# 05_LMS7002M_Misc.net
KiCad netlist of a schematic drawn in Altium Designer
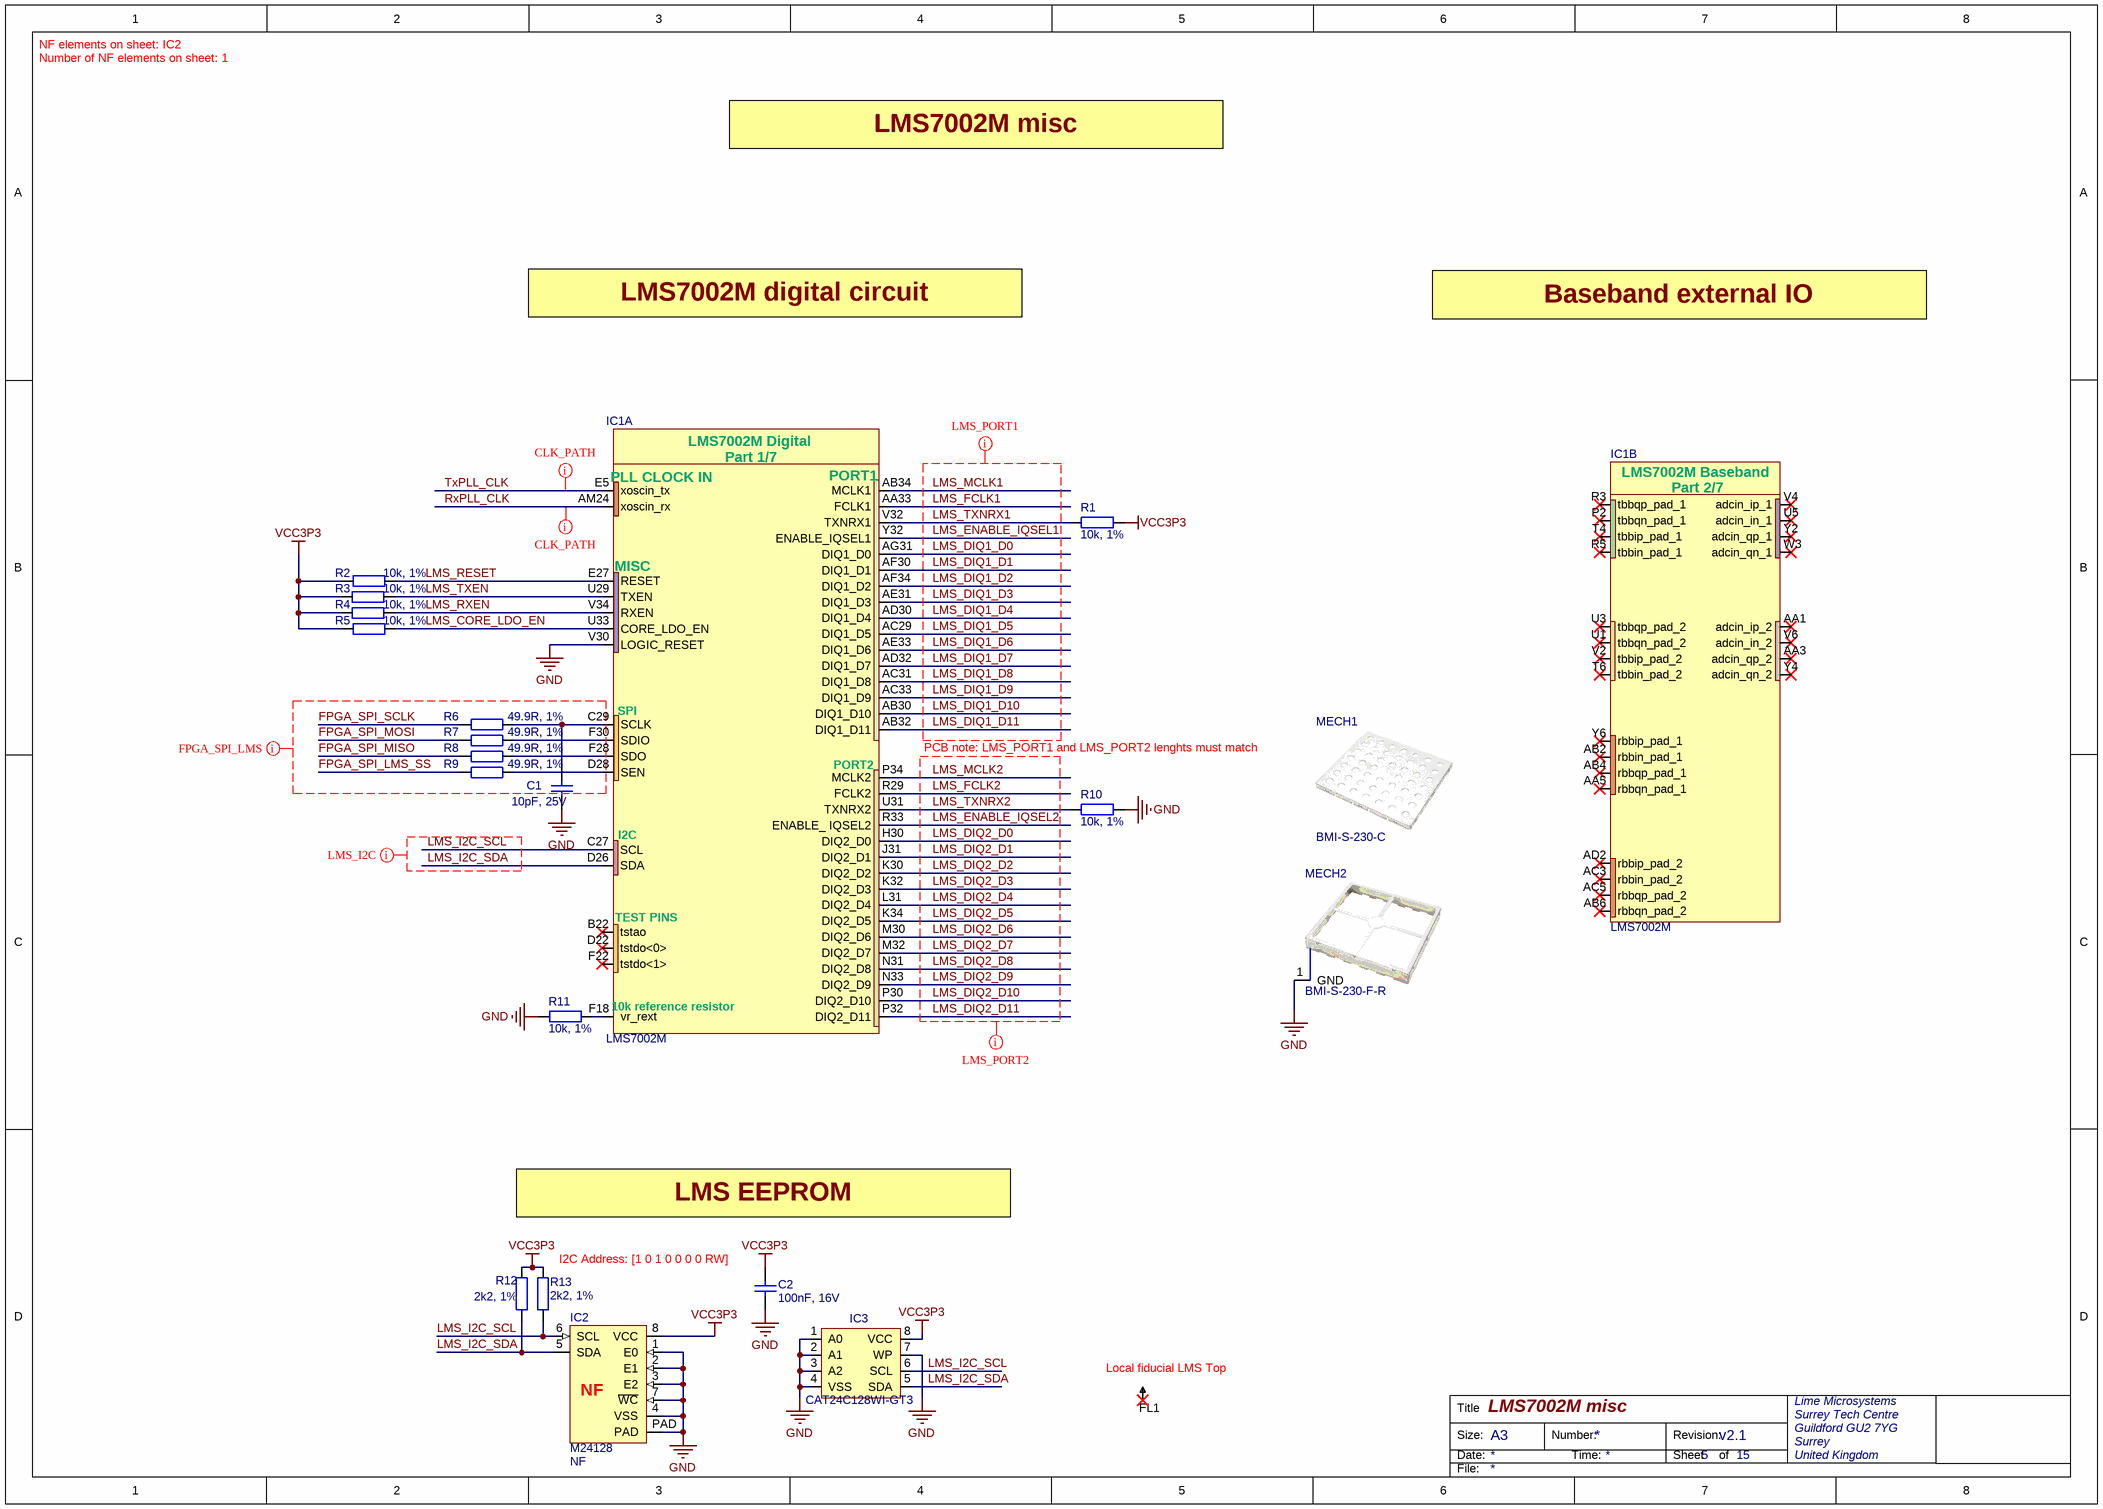
[diagram p0: 05_LMS7002M_Misc.SchDoc]

(export (version "E")
  (design (tool "Eeschema 10.0.6"))
  (components
    (comp (ref "C1")
      (value "10pF, 25V")
      (footprint "CAP0402")
      (fields (field (name "MANUFACTURER") "AVX"))
      (libsource (lib "LimeMicroAltiumLib_schLib") (part "Cap_0402"))
    )
    (comp (ref "C2")
      (value "100nF, 16V")
      (footprint "CAP0402")
      (fields (field (name "TOLERANCE") "10 %") (field (name "MANUFACTURER") "Murata Electronics"))
      (libsource (lib "LimeFPGAboard_schLib") (part "Cap_0603"))
    )
    (comp (ref "FL1")
      (value "Fiducial")
      (footprint "Fiducial_local")
      (libsource (lib "VGTU_Altium_lib") (part "Fiducial"))
    )
    (comp (ref "IC1")
      (value "LMS7002M")
      (footprint "LMS7002M_v5")
      (description "Schematic symbol revision 3. Default footprint - 0.31mm pad")
      (fields (field (name "MANUFACTURER") "Lime Microsystems"))
      (libsource (lib "LimeNet-Micro_2v1-SDR") (part "LMS7002Mr3"))
    )
    (comp (ref "IC2")
      (value "M24128")
      (footprint "M24128-DFMC6TG")
      (fields (field (name "MANUFACTURER") "STMicroelectronics") (field (name "ASSEMBLY INFO") "NF"))
      (libsource (lib "LimeMicroAltiumLib_schLib") (part "M24128-DFMC6TG"))
    )
    (comp (ref "IC3")
      (value "CAT24C128WI-GT3")
      (footprint "SOIC127P600-8DL_v2")
      (fields (field (name "MANUFACTURER") "ON Semiconductor") (field (name "BASE PART NUMBER") "CAT24C128"))
      (libsource (lib "LimeMicroAltiumLib_schLib") (part "24FC64F"))
    )
    (comp (ref "MECH1")
      (value "BMI-S-230-C")
      (fields (field (name "MANUFACTURER") "Laird Technologies EMI"))
      (libsource (lib "LimeMicroAltiumLib_schLib_r01") (part "RFI_SHIELD_2_cover"))
    )
    (comp (ref "MECH2")
      (value "BMI-S-230-F-R")
      (footprint "RFI_SHIELD_BMI-S-230-F-R")
      (fields (field (name "MANUFACTURER") "Laird Technologies EMI"))
      (libsource (lib "LimeMicroAltiumLib_schLib_r01") (part "RFI_SHIELD_2_frame"))
    )
    (comp (ref "R1")
      (value "10k, 1%")
      (footprint "RES0402")
      (fields (field (name "MANUFACTURER") "Yageo") (field (name "TOLERANCE") "±1%"))
      (libsource (lib "LimeMicroAltiumLib_schLib") (part "Res_0402"))
    )
    (comp (ref "R2")
      (value "10k, 1%")
      (footprint "RES0402")
      (fields (field (name "MANUFACTURER") "Yageo") (field (name "TOLERANCE") "±1%"))
      (libsource (lib "LimeMicroAltiumLib_schLib") (part "Res_0402"))
    )
    (comp (ref "R3")
      (value "10k, 1%")
      (footprint "RES0402")
      (fields (field (name "MANUFACTURER") "Yageo") (field (name "TOLERANCE") "±1%"))
      (libsource (lib "LimeMicroAltiumLib_schLib") (part "Res_0402"))
    )
    (comp (ref "R4")
      (value "10k, 1%")
      (footprint "RES0402")
      (fields (field (name "MANUFACTURER") "Yageo") (field (name "TOLERANCE") "±1%"))
      (libsource (lib "LimeMicroAltiumLib_schLib") (part "Res_0402"))
    )
    (comp (ref "R5")
      (value "10k, 1%")
      (footprint "RES0402")
      (fields (field (name "MANUFACTURER") "Yageo") (field (name "TOLERANCE") "±1%"))
      (libsource (lib "LimeMicroAltiumLib_schLib") (part "Res_0402"))
    )
    (comp (ref "R6")
      (value "49.9R, 1%")
      (footprint "RES0402")
      (fields
        (field (name "TOLERANCE") "±1%")
        (field (name "MANUFACTURER") "Samsung Electro-Mechanics America, Inc.")
      )
      (libsource (lib "LimeMicroAltiumLib_schLib") (part "Res_0402"))
    )
    (comp (ref "R7")
      (value "49.9R, 1%")
      (footprint "RES0402")
      (fields
        (field (name "TOLERANCE") "±1%")
        (field (name "MANUFACTURER") "Samsung Electro-Mechanics America, Inc.")
      )
      (libsource (lib "LimeMicroAltiumLib_schLib") (part "Res_0402"))
    )
    (comp (ref "R8")
      (value "49.9R, 1%")
      (footprint "RES0402")
      (fields
        (field (name "TOLERANCE") "±1%")
        (field (name "MANUFACTURER") "Samsung Electro-Mechanics America, Inc.")
      )
      (libsource (lib "LimeMicroAltiumLib_schLib") (part "Res_0402"))
    )
    (comp (ref "R9")
      (value "49.9R, 1%")
      (footprint "RES0402")
      (fields
        (field (name "TOLERANCE") "±1%")
        (field (name "MANUFACTURER") "Samsung Electro-Mechanics America, Inc.")
      )
      (libsource (lib "LimeMicroAltiumLib_schLib") (part "Res_0402"))
    )
    (comp (ref "R10")
      (value "10k, 1%")
      (footprint "RES0402")
      (fields (field (name "MANUFACTURER") "Yageo") (field (name "TOLERANCE") "±1%"))
      (libsource (lib "LimeMicroAltiumLib_schLib") (part "Res_0402"))
    )
    (comp (ref "R11")
      (value "10k, 1%")
      (footprint "RES0402")
      (fields (field (name "MANUFACTURER") "Yageo") (field (name "TOLERANCE") "±1%"))
      (libsource (lib "LimeMicroAltiumLib_schLib") (part "Res_0402"))
    )
    (comp (ref "R12")
      (value "2k2, 1%")
      (footprint "RES0402")
      (fields (field (name "MANUFACTURER") "Stackpole Electronics Inc") (field (name "TOLERANCE") "±1%"))
      (libsource (lib "LimeMicroAltiumLib_schLib") (part "Res_0402"))
    )
    (comp (ref "R13")
      (value "2k2, 1%")
      (footprint "RES0402")
      (fields (field (name "MANUFACTURER") "Stackpole Electronics Inc") (field (name "TOLERANCE") "±1%"))
      (libsource (lib "LimeMicroAltiumLib_schLib") (part "Res_0402"))
    )
  )
  (nets
    (net (code "1") (name "/FPGA_SPI_LMS_SS") (class "Default")
      (node (ref "R9") (pin "2") (pinfunction "2_2") (pintype "passive"))
    )
    (net (code "2") (name "/FPGA_SPI_MISO") (class "Default")
      (node (ref "R8") (pin "2") (pinfunction "2_2") (pintype "passive"))
    )
    (net (code "3") (name "/FPGA_SPI_MOSI") (class "Default")
      (node (ref "R7") (pin "2") (pinfunction "2_2") (pintype "passive"))
    )
    (net (code "4") (name "/FPGA_SPI_SCLK") (class "Default")
      (node (ref "R6") (pin "2") (pinfunction "2_2") (pintype "passive"))
    )
    (net (code "5") (name "/LMS_CORE_LDO_EN") (class "Default")
      (node (ref "IC1") (pin "U33") (pinfunction "CORE_LDO_EN_U33") (pintype "passive"))
      (node (ref "R5") (pin "1") (pinfunction "1_1") (pintype "passive"))
    )
    (net (code "6") (name "/LMS_DIQ1_D0") (class "Default")
      (node (ref "IC1") (pin "AG31") (pinfunction "DIQ1_D0_AG31") (pintype "passive"))
    )
    (net (code "7") (name "/LMS_DIQ1_D1") (class "Default")
      (node (ref "IC1") (pin "AF30") (pinfunction "DIQ1_D1_AF30") (pintype "passive"))
    )
    (net (code "8") (name "/LMS_DIQ1_D2") (class "Default")
      (node (ref "IC1") (pin "AF34") (pinfunction "DIQ1_D2_AF34") (pintype "passive"))
    )
    (net (code "9") (name "/LMS_DIQ1_D3") (class "Default")
      (node (ref "IC1") (pin "AE31") (pinfunction "DIQ1_D3_AE31") (pintype "passive"))
    )
    (net (code "10") (name "/LMS_DIQ1_D4") (class "Default")
      (node (ref "IC1") (pin "AD30") (pinfunction "DIQ1_D4_AD30") (pintype "passive"))
    )
    (net (code "11") (name "/LMS_DIQ1_D5") (class "Default")
      (node (ref "IC1") (pin "AC29") (pinfunction "DIQ1_D5_AC29") (pintype "passive"))
    )
    (net (code "12") (name "/LMS_DIQ1_D6") (class "Default")
      (node (ref "IC1") (pin "AE33") (pinfunction "DIQ1_D6_AE33") (pintype "passive"))
    )
    (net (code "13") (name "/LMS_DIQ1_D7") (class "Default")
      (node (ref "IC1") (pin "AD32") (pinfunction "DIQ1_D7_AD32") (pintype "passive"))
    )
    (net (code "14") (name "/LMS_DIQ1_D8") (class "Default")
      (node (ref "IC1") (pin "AC31") (pinfunction "DIQ1_D8_AC31") (pintype "passive"))
    )
    (net (code "15") (name "/LMS_DIQ1_D9") (class "Default")
      (node (ref "IC1") (pin "AC33") (pinfunction "DIQ1_D9_AC33") (pintype "passive"))
    )
    (net (code "16") (name "/LMS_DIQ1_D10") (class "Default")
      (node (ref "IC1") (pin "AB30") (pinfunction "DIQ1_D10_AB30") (pintype "passive"))
    )
    (net (code "17") (name "/LMS_DIQ1_D11") (class "Default")
      (node (ref "IC1") (pin "AB32") (pinfunction "DIQ1_D11_AB32") (pintype "passive"))
    )
    (net (code "18") (name "/LMS_DIQ2_D0") (class "Default")
      (node (ref "IC1") (pin "H30") (pinfunction "DIQ2_D0_H30") (pintype "passive"))
    )
    (net (code "19") (name "/LMS_DIQ2_D1") (class "Default")
      (node (ref "IC1") (pin "J31") (pinfunction "DIQ2_D1_J31") (pintype "passive"))
    )
    (net (code "20") (name "/LMS_DIQ2_D2") (class "Default")
      (node (ref "IC1") (pin "K30") (pinfunction "DIQ2_D2_K30") (pintype "passive"))
    )
    (net (code "21") (name "/LMS_DIQ2_D3") (class "Default")
      (node (ref "IC1") (pin "K32") (pinfunction "DIQ2_D3_K32") (pintype "passive"))
    )
    (net (code "22") (name "/LMS_DIQ2_D4") (class "Default")
      (node (ref "IC1") (pin "L31") (pinfunction "DIQ2_D4_L31") (pintype "passive"))
    )
    (net (code "23") (name "/LMS_DIQ2_D5") (class "Default")
      (node (ref "IC1") (pin "K34") (pinfunction "DIQ2_D5_K34") (pintype "passive"))
    )
    (net (code "24") (name "/LMS_DIQ2_D6") (class "Default")
      (node (ref "IC1") (pin "M30") (pinfunction "DIQ2_D6_M30") (pintype "passive"))
    )
    (net (code "25") (name "/LMS_DIQ2_D7") (class "Default")
      (node (ref "IC1") (pin "M32") (pinfunction "DIQ2_D7_M32") (pintype "passive"))
    )
    (net (code "26") (name "/LMS_DIQ2_D8") (class "Default")
      (node (ref "IC1") (pin "N31") (pinfunction "DIQ2_D8_N31") (pintype "passive"))
    )
    (net (code "27") (name "/LMS_DIQ2_D9") (class "Default")
      (node (ref "IC1") (pin "N33") (pinfunction "DIQ2_D9_N33") (pintype "passive"))
    )
    (net (code "28") (name "/LMS_DIQ2_D10") (class "Default")
      (node (ref "IC1") (pin "P30") (pinfunction "DIQ2_D10_P30") (pintype "passive"))
    )
    (net (code "29") (name "/LMS_DIQ2_D11") (class "Default")
      (node (ref "IC1") (pin "P32") (pinfunction "DIQ2_D11_P32") (pintype "passive"))
    )
    (net (code "30") (name "/LMS_ENABLE_IQSEL1") (class "Default")
      (node (ref "IC1") (pin "Y32") (pinfunction "ENABLE_IQSEL1_Y32") (pintype "passive"))
    )
    (net (code "31") (name "/LMS_ENABLE_IQSEL2") (class "Default")
      (node (ref "IC1") (pin "R33") (pinfunction "ENABLE__IQSEL2_R33") (pintype "passive"))
    )
    (net (code "32") (name "/LMS_FCLK1") (class "Default")
      (node (ref "IC1") (pin "AA33") (pinfunction "FCLK1_AA33") (pintype "passive"))
    )
    (net (code "33") (name "/LMS_FCLK2") (class "Default")
      (node (ref "IC1") (pin "R29") (pinfunction "FCLK2_R29") (pintype "passive"))
    )
    (net (code "34") (name "/LMS_I2C_SCL") (class "Default")
      (node (ref "IC1") (pin "C27") (pinfunction "SCL_C27") (pintype "passive"))
      (node (ref "IC2") (pin "6") (pinfunction "SCL_6") (pintype "input"))
      (node (ref "IC3") (pin "6") (pinfunction "SCL_6") (pintype "passive"))
      (node (ref "R13") (pin "2") (pinfunction "2_2") (pintype "passive"))
    )
    (net (code "35") (name "/LMS_I2C_SDA") (class "Default")
      (node (ref "IC1") (pin "D26") (pinfunction "SDA_D26") (pintype "passive"))
      (node (ref "IC2") (pin "5") (pinfunction "SDA_5") (pintype "bidirectional"))
      (node (ref "IC3") (pin "5") (pinfunction "SDA_5") (pintype "passive"))
      (node (ref "R12") (pin "2") (pinfunction "2_2") (pintype "passive"))
    )
    (net (code "36") (name "/LMS_MCLK1") (class "Default")
      (node (ref "IC1") (pin "AB34") (pinfunction "MCLK1_AB34") (pintype "passive"))
    )
    (net (code "37") (name "/LMS_MCLK2") (class "Default")
      (node (ref "IC1") (pin "P34") (pinfunction "MCLK2_P34") (pintype "passive"))
    )
    (net (code "38") (name "/LMS_RESET") (class "Default")
      (node (ref "IC1") (pin "E27") (pinfunction "RESET_E27") (pintype "passive"))
      (node (ref "R2") (pin "1") (pinfunction "1_1") (pintype "passive"))
    )
    (net (code "39") (name "/LMS_RXEN") (class "Default")
      (node (ref "IC1") (pin "V34") (pinfunction "RXEN_V34") (pintype "passive"))
      (node (ref "R4") (pin "2") (pinfunction "2_2") (pintype "passive"))
    )
    (net (code "40") (name "/LMS_TXEN") (class "Default")
      (node (ref "IC1") (pin "U29") (pinfunction "TXEN_U29") (pintype "passive"))
      (node (ref "R3") (pin "2") (pinfunction "2_2") (pintype "passive"))
    )
    (net (code "41") (name "/LMS_TXNRX1") (class "Default")
      (node (ref "IC1") (pin "V32") (pinfunction "TXNRX1_V32") (pintype "passive"))
      (node (ref "R1") (pin "1") (pinfunction "1_1") (pintype "passive"))
    )
    (net (code "42") (name "/LMS_TXNRX2") (class "Default")
      (node (ref "IC1") (pin "U31") (pinfunction "TXNRX2_U31") (pintype "passive"))
      (node (ref "R10") (pin "1") (pinfunction "1_1") (pintype "passive"))
    )
    (net (code "43") (name "/RxPLL_CLK") (class "Default")
      (node (ref "IC1") (pin "AM24") (pinfunction "xoscin_rx_AM24") (pintype "passive"))
    )
    (net (code "44") (name "/TxPLL_CLK") (class "Default")
      (node (ref "IC1") (pin "E5") (pinfunction "xoscin_tx_E5") (pintype "passive"))
    )
    (net (code "45") (name "GND") (class "Default")
      (node (ref "C1") (pin "2") (pinfunction "2_2") (pintype "passive"))
      (node (ref "C2") (pin "2") (pinfunction "2_2") (pintype "passive"))
      (node (ref "IC1") (pin "V30") (pinfunction "LOGIC_RESET_V30") (pintype "passive"))
      (node (ref "IC2") (pin "1") (pinfunction "E0_1") (pintype "input"))
      (node (ref "IC2") (pin "2") (pinfunction "E1_2") (pintype "input"))
      (node (ref "IC2") (pin "3") (pinfunction "E2_3") (pintype "input"))
      (node (ref "IC2") (pin "4") (pinfunction "VSS_4") (pintype "power_in"))
      (node (ref "IC2") (pin "7") (pinfunction "~{WC}_7") (pintype "input"))
      (node (ref "IC2") (pin "PAD") (pinfunction "PAD_PAD") (pintype "power_in"))
      (node (ref "IC3") (pin "1") (pinfunction "A0_1") (pintype "passive"))
      (node (ref "IC3") (pin "2") (pinfunction "A1_2") (pintype "passive"))
      (node (ref "IC3") (pin "3") (pinfunction "A2_3") (pintype "passive"))
      (node (ref "IC3") (pin "4") (pinfunction "VSS_4") (pintype "passive"))
      (node (ref "IC3") (pin "7") (pinfunction "WP_7") (pintype "passive"))
      (node (ref "MECH2") (pin "1") (pinfunction "GND_1") (pintype "passive"))
      (node (ref "R10") (pin "2") (pinfunction "2_2") (pintype "passive"))
      (node (ref "R11") (pin "2") (pinfunction "2_2") (pintype "passive"))
    )
    (net (code "46") (name "Net-(IC1A-SCLK)") (class "Default")
      (node (ref "C1") (pin "1") (pinfunction "1_1") (pintype "passive"))
      (node (ref "IC1") (pin "C29") (pinfunction "SCLK_C29") (pintype "passive"))
      (node (ref "R6") (pin "1") (pinfunction "1_1") (pintype "passive"))
    )
    (net (code "47") (name "Net-(IC1A-SDIO)") (class "Default")
      (node (ref "IC1") (pin "F30") (pinfunction "SDIO_F30") (pintype "passive"))
      (node (ref "R7") (pin "1") (pinfunction "1_1") (pintype "passive"))
    )
    (net (code "48") (name "Net-(IC1A-SDO)") (class "Default")
      (node (ref "IC1") (pin "F28") (pinfunction "SDO_F28") (pintype "passive"))
      (node (ref "R8") (pin "1") (pinfunction "1_1") (pintype "passive"))
    )
    (net (code "49") (name "Net-(IC1A-SEN)") (class "Default")
      (node (ref "IC1") (pin "D28") (pinfunction "SEN_D28") (pintype "passive"))
      (node (ref "R9") (pin "1") (pinfunction "1_1") (pintype "passive"))
    )
    (net (code "50") (name "Net-(IC1A-vr_rext)") (class "Default")
      (node (ref "IC1") (pin "F18") (pinfunction "vr_rext_F18") (pintype "passive"))
      (node (ref "R11") (pin "1") (pinfunction "1_1") (pintype "passive"))
    )
    (net (code "51") (name "VCC3P3") (class "Default")
      (node (ref "C2") (pin "1") (pinfunction "1_1") (pintype "passive"))
      (node (ref "IC2") (pin "8") (pinfunction "VCC_8") (pintype "power_in"))
      (node (ref "IC3") (pin "8") (pinfunction "VCC_8") (pintype "passive"))
      (node (ref "R1") (pin "2") (pinfunction "2_2") (pintype "passive"))
      (node (ref "R12") (pin "1") (pinfunction "1_1") (pintype "passive"))
      (node (ref "R13") (pin "1") (pinfunction "1_1") (pintype "passive"))
      (node (ref "R2") (pin "2") (pinfunction "2_2") (pintype "passive"))
      (node (ref "R3") (pin "1") (pinfunction "1_1") (pintype "passive"))
      (node (ref "R4") (pin "1") (pinfunction "1_1") (pintype "passive"))
      (node (ref "R5") (pin "2") (pinfunction "2_2") (pintype "passive"))
    )
    (net (code "52") (name "unconnected-(FL1-Pad1)") (class "Default")
      (node (ref "FL1") (pin "1") (pintype "passive+no_connect"))
    )
    (net (code "53") (name "unconnected-(IC1A-tstao-PadB22)") (class "Default")
      (node (ref "IC1") (pin "B22") (pinfunction "tstao_B22") (pintype "passive+no_connect"))
    )
    (net (code "54") (name "unconnected-(IC1A-tstdo<0>-PadD22)") (class "Default")
      (node (ref "IC1") (pin "D22") (pinfunction "tstdo<0>_D22") (pintype "passive+no_connect"))
    )
    (net (code "55") (name "unconnected-(IC1A-tstdo<1>-PadF22)") (class "Default")
      (node (ref "IC1") (pin "F22") (pinfunction "tstdo<1>_F22") (pintype "passive+no_connect"))
    )
    (net (code "56") (name "unconnected-(IC1B-adcin_in_1-PadU5)") (class "Default")
      (node (ref "IC1") (pin "U5") (pinfunction "adcin_in_1_U5") (pintype "passive+no_connect"))
    )
    (net (code "57") (name "unconnected-(IC1B-adcin_in_2-PadV6)") (class "Default")
      (node (ref "IC1") (pin "V6") (pinfunction "adcin_in_2_V6") (pintype "passive+no_connect"))
    )
    (net (code "58") (name "unconnected-(IC1B-adcin_ip_1-PadV4)") (class "Default")
      (node (ref "IC1") (pin "V4") (pinfunction "adcin_ip_1_V4") (pintype "passive+no_connect"))
    )
    (net (code "59") (name "unconnected-(IC1B-adcin_ip_2-PadAA1)") (class "Default")
      (node (ref "IC1") (pin "AA1") (pinfunction "adcin_ip_2_AA1") (pintype "passive+no_connect"))
    )
    (net (code "60") (name "unconnected-(IC1B-adcin_qn_1-PadW3)") (class "Default")
      (node (ref "IC1") (pin "W3") (pinfunction "adcin_qn_1_W3") (pintype "passive+no_connect"))
    )
    (net (code "61") (name "unconnected-(IC1B-adcin_qn_2-PadY4)") (class "Default")
      (node (ref "IC1") (pin "Y4") (pinfunction "adcin_qn_2_Y4") (pintype "passive+no_connect"))
    )
    (net (code "62") (name "unconnected-(IC1B-adcin_qp_1-PadY2)") (class "Default")
      (node (ref "IC1") (pin "Y2") (pinfunction "adcin_qp_1_Y2") (pintype "passive+no_connect"))
    )
    (net (code "63") (name "unconnected-(IC1B-adcin_qp_2-PadAA3)") (class "Default")
      (node (ref "IC1") (pin "AA3") (pinfunction "adcin_qp_2_AA3") (pintype "passive+no_connect"))
    )
    (net (code "64") (name "unconnected-(IC1B-rbbin_pad_1-PadAB2)") (class "Default")
      (node (ref "IC1") (pin "AB2") (pinfunction "rbbin_pad_1_AB2") (pintype "passive+no_connect"))
    )
    (net (code "65") (name "unconnected-(IC1B-rbbin_pad_2-PadAC3)") (class "Default")
      (node (ref "IC1") (pin "AC3") (pinfunction "rbbin_pad_2_AC3") (pintype "passive+no_connect"))
    )
    (net (code "66") (name "unconnected-(IC1B-rbbip_pad_1-PadY6)") (class "Default")
      (node (ref "IC1") (pin "Y6") (pinfunction "rbbip_pad_1_Y6") (pintype "passive+no_connect"))
    )
    (net (code "67") (name "unconnected-(IC1B-rbbip_pad_2-PadAD2)") (class "Default")
      (node (ref "IC1") (pin "AD2") (pinfunction "rbbip_pad_2_AD2") (pintype "passive+no_connect"))
    )
    (net (code "68") (name "unconnected-(IC1B-rbbqn_pad_1-PadAA5)") (class "Default")
      (node (ref "IC1") (pin "AA5") (pinfunction "rbbqn_pad_1_AA5") (pintype "passive+no_connect"))
    )
    (net (code "69") (name "unconnected-(IC1B-rbbqn_pad_2-PadAB6)") (class "Default")
      (node (ref "IC1") (pin "AB6") (pinfunction "rbbqn_pad_2_AB6") (pintype "passive+no_connect"))
    )
    (net (code "70") (name "unconnected-(IC1B-rbbqp_pad_1-PadAB4)") (class "Default")
      (node (ref "IC1") (pin "AB4") (pinfunction "rbbqp_pad_1_AB4") (pintype "passive+no_connect"))
    )
    (net (code "71") (name "unconnected-(IC1B-rbbqp_pad_2-PadAC5)") (class "Default")
      (node (ref "IC1") (pin "AC5") (pinfunction "rbbqp_pad_2_AC5") (pintype "passive+no_connect"))
    )
    (net (code "72") (name "unconnected-(IC1B-tbbin_pad_1-PadR5)") (class "Default")
      (node (ref "IC1") (pin "R5") (pinfunction "tbbin_pad_1_R5") (pintype "passive+no_connect"))
    )
    (net (code "73") (name "unconnected-(IC1B-tbbin_pad_2-PadT6)") (class "Default")
      (node (ref "IC1") (pin "T6") (pinfunction "tbbin_pad_2_T6") (pintype "passive+no_connect"))
    )
    (net (code "74") (name "unconnected-(IC1B-tbbip_pad_1-PadT4)") (class "Default")
      (node (ref "IC1") (pin "T4") (pinfunction "tbbip_pad_1_T4") (pintype "passive+no_connect"))
    )
    (net (code "75") (name "unconnected-(IC1B-tbbip_pad_2-PadV2)") (class "Default")
      (node (ref "IC1") (pin "V2") (pinfunction "tbbip_pad_2_V2") (pintype "passive+no_connect"))
    )
    (net (code "76") (name "unconnected-(IC1B-tbbqn_pad_1-PadP2)") (class "Default")
      (node (ref "IC1") (pin "P2") (pinfunction "tbbqn_pad_1_P2") (pintype "passive+no_connect"))
    )
    (net (code "77") (name "unconnected-(IC1B-tbbqn_pad_2-PadU1)") (class "Default")
      (node (ref "IC1") (pin "U1") (pinfunction "tbbqn_pad_2_U1") (pintype "passive+no_connect"))
    )
    (net (code "78") (name "unconnected-(IC1B-tbbqp_pad_1-PadR3)") (class "Default")
      (node (ref "IC1") (pin "R3") (pinfunction "tbbqp_pad_1_R3") (pintype "passive+no_connect"))
    )
    (net (code "79") (name "unconnected-(IC1B-tbbqp_pad_2-PadU3)") (class "Default")
      (node (ref "IC1") (pin "U3") (pinfunction "tbbqp_pad_2_U3") (pintype "passive+no_connect"))
    )
  )
)
